# MCU.net
KiCad netlist of a schematic drawn in Altium Designer
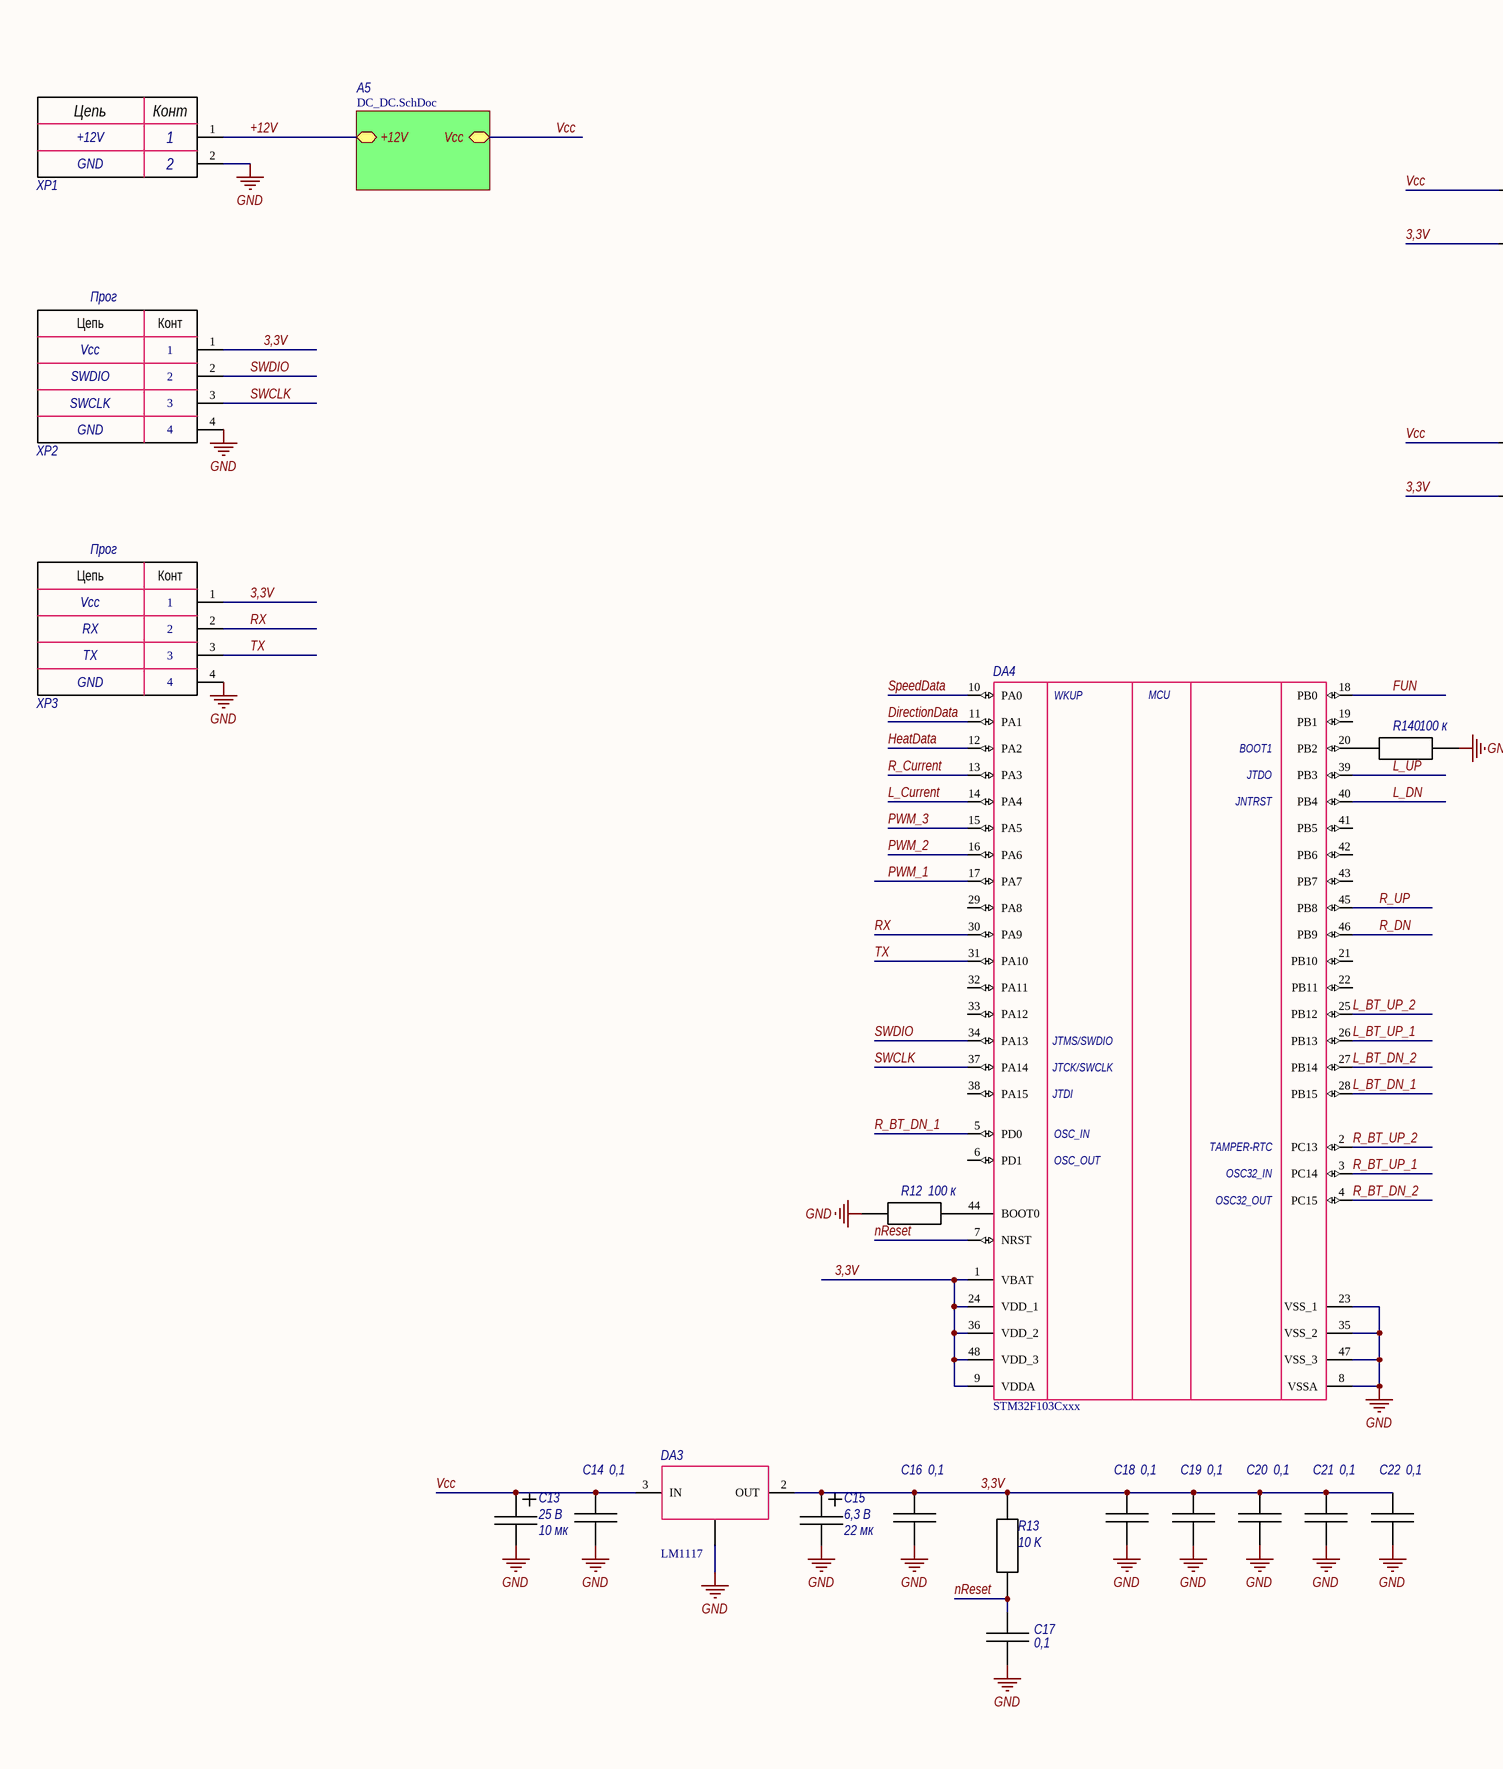
[diagram p0: MCU.SchDoc, left]
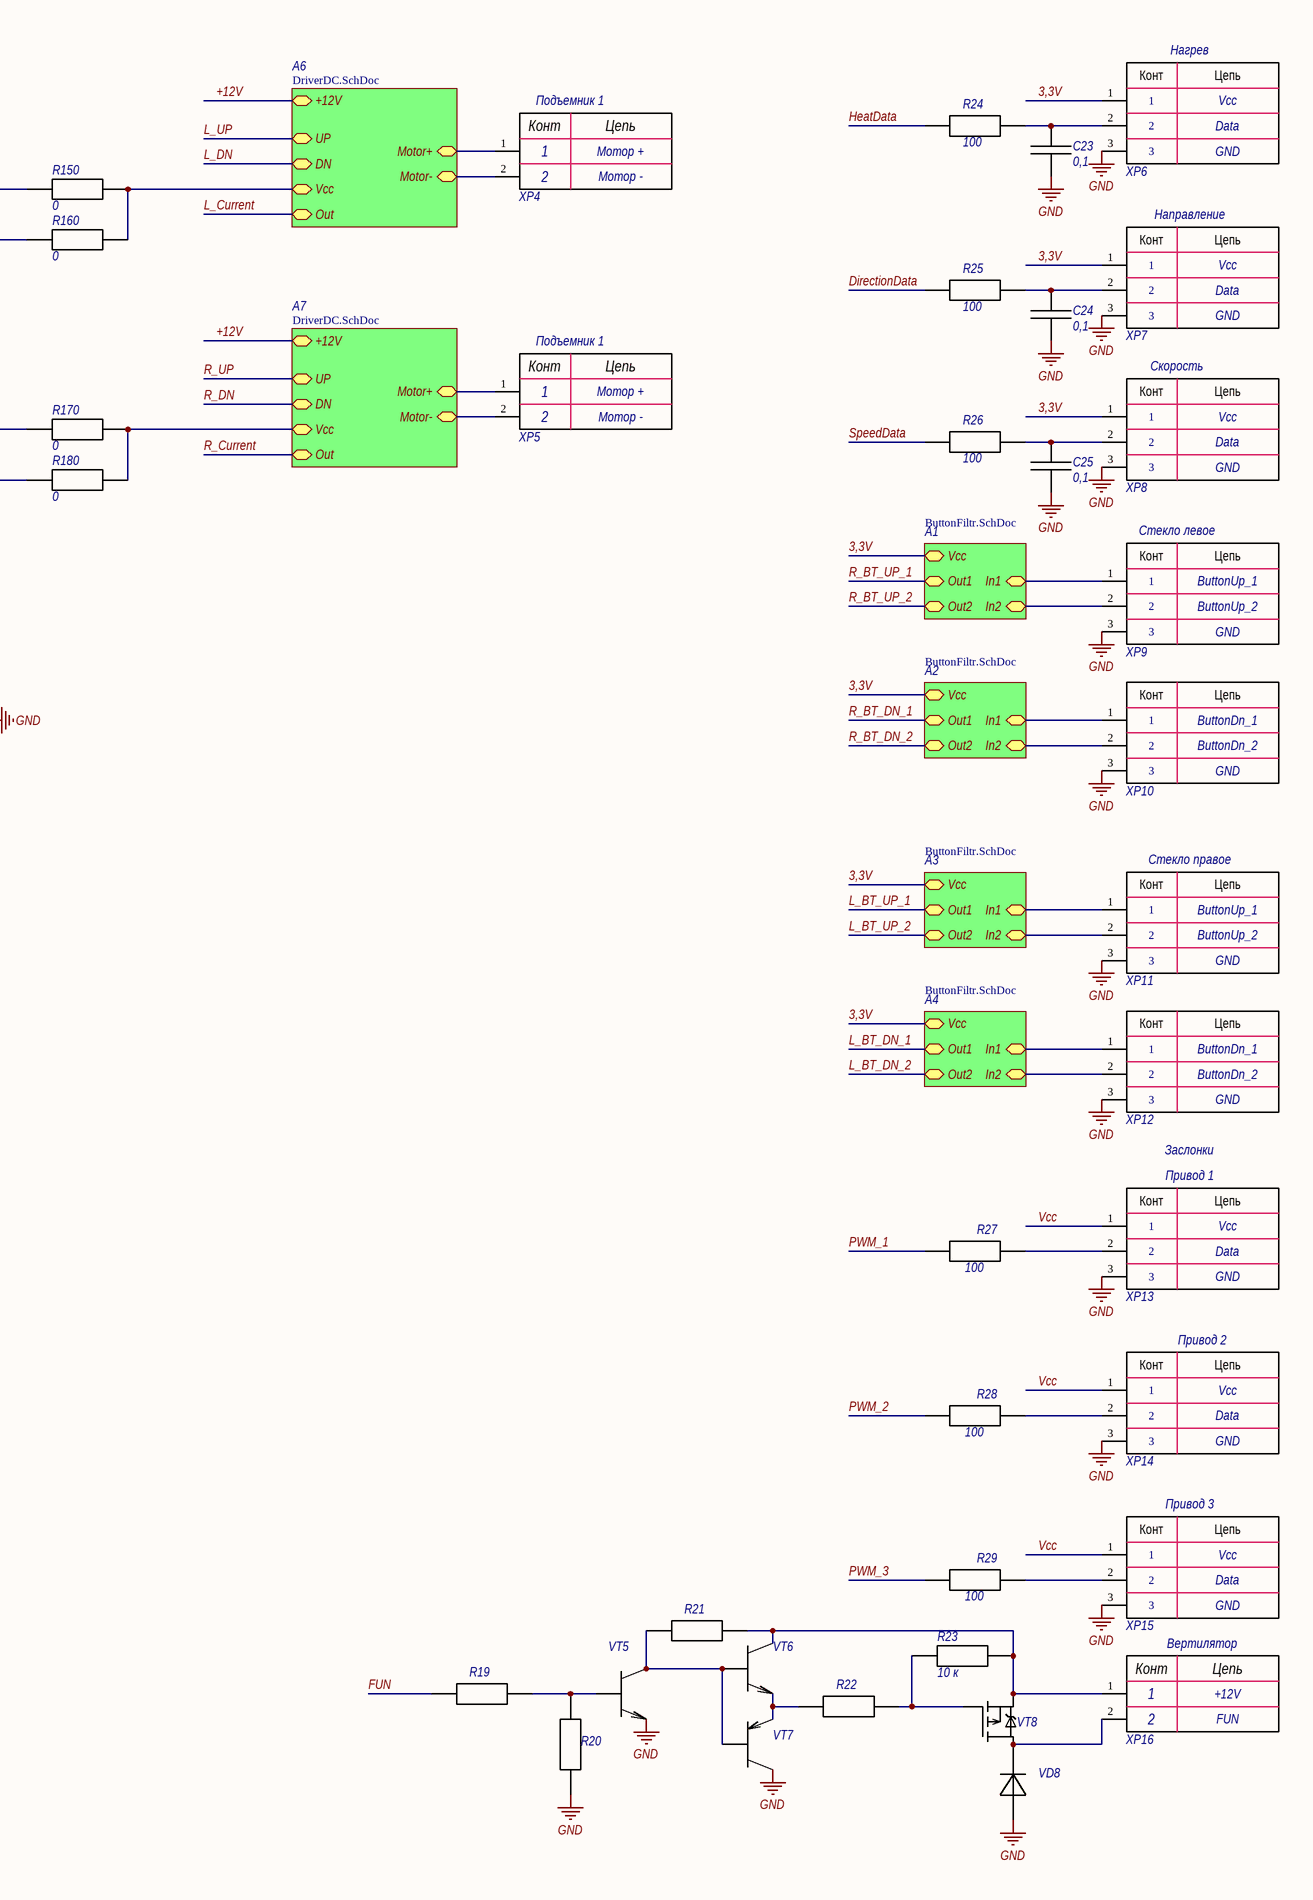
[diagram p1: MCU.SchDoc, right]

(export (version "E")
  (design (tool "Eeschema 10.0.6"))
  (components
    (comp (ref "C13")
      (value "Конденсаторы танталовые")
      (footprint "B-B")
      (fields
        (field (name "PART NUMBER") "Конденсатор танталовый 10 мкФ 25 В \"B\" +/- 10% T491B106K025AT \"KEMET\"")
        (field (name "MANUFACTURER") "\"KEMET\"")
        (field (name "MANUFACTURERPARTNUMBER") "T491B106K025AT")
        (field (name "POWER/VOLTAGE") "25 В")
        (field (name "VALUE SCH") "10 мк")
      )
      (libsource (lib "Library") (part "Конденсаторы танталовые"))
    )
    (comp (ref "C14")
      (value "Конденсаторы керамические")
      (footprint "C0603_autoMount")
      (fields
        (field (name "PART NUMBER") "Чип. керам. 0603 0,1 мкФ 50 В +/-10% X7R CC0603KKX7R9BB104 \"Yageo\"")
        (field (name "MANUFACTURER") "\"Yageo\"")
        (field (name "MANUFACTURERPARTNUMBER") "CC0603KKX7R9BB104")
        (field (name "VALUE SCH") "0,1")
      )
      (libsource (lib "Library") (part "Конденсаторы керамические"))
    )
    (comp (ref "C15")
      (value "Конденсаторы танталовые")
      (footprint "A-A")
      (fields
        (field (name "PART NUMBER") "Конденсатор танталовый 22 мкФ 6,3 В \"A\" +/- 10% TAJA226K006 \"Kyocera AVX\"")
        (field (name "MANUFACTURER") "\"Kyocera AVX\"")
        (field (name "MANUFACTURERPARTNUMBER") "TAJA226K006")
        (field (name "POWER/VOLTAGE") "6,3 В")
        (field (name "VALUE SCH") "22 мк")
      )
      (libsource (lib "Library") (part "Конденсаторы танталовые"))
    )
    (comp (ref "C16")
      (value "Конденсаторы керамические")
      (footprint "C0603_autoMount")
      (fields
        (field (name "PART NUMBER") "Чип. керам. 0603 0,1 мкФ 50 В +/-10% X7R CC0603KKX7R9BB104 \"Yageo\"")
        (field (name "MANUFACTURER") "\"Yageo\"")
        (field (name "MANUFACTURERPARTNUMBER") "CC0603KKX7R9BB104")
        (field (name "VALUE SCH") "0,1")
      )
      (libsource (lib "Library") (part "Конденсаторы керамические"))
    )
    (comp (ref "C17")
      (value "Конденсаторы керамические")
      (footprint "C0603_autoMount")
      (fields
        (field (name "PART NUMBER") "Чип. керам. 0603 0,1 мкФ 50 В +/-10% X7R CC0603KKX7R9BB104 \"Yageo\"")
        (field (name "MANUFACTURER") "\"Yageo\"")
        (field (name "MANUFACTURERPARTNUMBER") "CC0603KKX7R9BB104")
        (field (name "VALUE SCH") "0,1")
      )
      (libsource (lib "Library") (part "Конденсаторы керамические"))
    )
    (comp (ref "C18")
      (value "Конденсаторы керамические")
      (footprint "C0603_autoMount")
      (fields
        (field (name "PART NUMBER") "Чип. керам. 0603 0,1 мкФ 50 В +/-10% X7R CC0603KKX7R9BB104 \"Yageo\"")
        (field (name "MANUFACTURER") "\"Yageo\"")
        (field (name "MANUFACTURERPARTNUMBER") "CC0603KKX7R9BB104")
        (field (name "VALUE SCH") "0,1")
      )
      (libsource (lib "Library") (part "Конденсаторы керамические"))
    )
    (comp (ref "C19")
      (value "Конденсаторы керамические")
      (footprint "C0603_autoMount")
      (fields
        (field (name "PART NUMBER") "Чип. керам. 0603 0,1 мкФ 50 В +/-10% X7R CC0603KKX7R9BB104 \"Yageo\"")
        (field (name "MANUFACTURER") "\"Yageo\"")
        (field (name "MANUFACTURERPARTNUMBER") "CC0603KKX7R9BB104")
        (field (name "VALUE SCH") "0,1")
      )
      (libsource (lib "Library") (part "Конденсаторы керамические"))
    )
    (comp (ref "C20")
      (value "Конденсаторы керамические")
      (footprint "C0603_autoMount")
      (fields
        (field (name "PART NUMBER") "Чип. керам. 0603 0,1 мкФ 50 В +/-10% X7R CC0603KKX7R9BB104 \"Yageo\"")
        (field (name "MANUFACTURER") "\"Yageo\"")
        (field (name "MANUFACTURERPARTNUMBER") "CC0603KKX7R9BB104")
        (field (name "VALUE SCH") "0,1")
      )
      (libsource (lib "Library") (part "Конденсаторы керамические"))
    )
    (comp (ref "C21")
      (value "Конденсаторы керамические")
      (footprint "C0603_autoMount")
      (fields
        (field (name "PART NUMBER") "Чип. керам. 0603 0,1 мкФ 50 В +/-10% X7R CC0603KKX7R9BB104 \"Yageo\"")
        (field (name "MANUFACTURER") "\"Yageo\"")
        (field (name "MANUFACTURERPARTNUMBER") "CC0603KKX7R9BB104")
        (field (name "VALUE SCH") "0,1")
      )
      (libsource (lib "Library") (part "Конденсаторы керамические"))
    )
    (comp (ref "C22")
      (value "Конденсаторы керамические")
      (footprint "C0603_autoMount")
      (fields
        (field (name "PART NUMBER") "Чип. керам. 0603 0,1 мкФ 50 В +/-10% X7R CC0603KKX7R9BB104 \"Yageo\"")
        (field (name "MANUFACTURER") "\"Yageo\"")
        (field (name "MANUFACTURERPARTNUMBER") "CC0603KKX7R9BB104")
        (field (name "VALUE SCH") "0,1")
      )
      (libsource (lib "Library") (part "Конденсаторы керамические"))
    )
    (comp (ref "C23")
      (value "Конденсаторы керамические")
      (footprint "C0603_autoMount")
      (fields
        (field (name "PART NUMBER") "Чип. керам. 0603 0,1 мкФ 50 В +/-10% X7R CC0603KKX7R9BB104 \"Yageo\"")
        (field (name "MANUFACTURER") "\"Yageo\"")
        (field (name "MANUFACTURERPARTNUMBER") "CC0603KKX7R9BB104")
        (field (name "VALUE SCH") "0,1")
      )
      (libsource (lib "Library") (part "Конденсаторы керамические"))
    )
    (comp (ref "C24")
      (value "Конденсаторы керамические")
      (footprint "C0603_autoMount")
      (fields
        (field (name "PART NUMBER") "Чип. керам. 0603 0,1 мкФ 50 В +/-10% X7R CC0603KKX7R9BB104 \"Yageo\"")
        (field (name "MANUFACTURER") "\"Yageo\"")
        (field (name "MANUFACTURERPARTNUMBER") "CC0603KKX7R9BB104")
        (field (name "VALUE SCH") "0,1")
      )
      (libsource (lib "Library") (part "Конденсаторы керамические"))
    )
    (comp (ref "C25")
      (value "Конденсаторы керамические")
      (footprint "C0603_autoMount")
      (fields
        (field (name "PART NUMBER") "Чип. керам. 0603 0,1 мкФ 50 В +/-10% X7R CC0603KKX7R9BB104 \"Yageo\"")
        (field (name "MANUFACTURER") "\"Yageo\"")
        (field (name "MANUFACTURERPARTNUMBER") "CC0603KKX7R9BB104")
        (field (name "VALUE SCH") "0,1")
      )
      (libsource (lib "Library") (part "Конденсаторы керамические"))
    )
    (comp (ref "DA3")
      (value "LM1117")
      (footprint "SOT223")
      (fields
        (field (name "PART NUMBER") "Стабилизатор AMS1117-3.3 \"Advanced Monolithic Systems\" SOT-223")
        (field (name "MANUFACTURER") "\"Advanced Monolithic Systems\"")
        (field (name "MANUFACTURERPARTNUMBER") "AMS1117-3.3")
      )
      (libsource (lib "Library") (part "LM1117"))
    )
    (comp (ref "DA4")
      (value "STM32F103Cxxx")
      (footprint "TQFP_48")
      (fields
        (field (name "PART NUMBER") "Микросхема CH32F103C8T6 \"WinChip\" TQFP-48")
        (field (name "MANUFACTURER") "\"WinChip\"")
        (field (name "MANUFACTURERPARTNUMBER") "CH32F103C8T6")
      )
      (libsource (lib "Library") (part "STM32F103Cxxx"))
    )
    (comp (ref "R12")
      (value "Resistor")
      (footprint "R0603_autoMount")
      (fields
        (field (name "PART NUMBER") "Чип рез. 0603 100 кОм  +/-1% RC0603FR-07100KL \"Yageo\"")
        (field (name "MANUFACTURER") "\"Yageo\"")
        (field (name "MANUFACTURERPARTNUMBER") "RC0603FR-07100KL")
        (field (name "VALUE SСH") "100 к")
      )
      (libsource (lib "Library") (part "Resistor"))
    )
    (comp (ref "R13")
      (value "Resistor")
      (footprint "R0603_autoMount")
      (fields
        (field (name "PART NUMBER") "Чип рез. 0603 10 кОм  +/-1% RC0603FR-0710KL \"Yageo\"")
        (field (name "MANUFACTURER") "\"Yageo\"")
        (field (name "MANUFACTURERPARTNUMBER") "RC0603FR-0710KL")
        (field (name "VALUE EURO") "10 K")
      )
      (libsource (lib "Library") (part "Resistor"))
    )
    (comp (ref "R19")
      (value "Resistor")
      (footprint "R0603_autoMount")
      (fields
        (field (name "PART NUMBER") "Чип рез. 0603 1 кОм  +/-1% RC0603FR-071KL \"Yageo\"")
        (field (name "MANUFACTURER") "\"Yageo\"")
        (field (name "MANUFACTURERPARTNUMBER") "RC0603FR-071KL")
      )
      (libsource (lib "Library") (part "Resistor"))
    )
    (comp (ref "R20")
      (value "Resistor")
      (footprint "R0603_autoMount")
      (fields
        (field (name "PART NUMBER") "Чип рез. 0603 10 кОм  +/-1% RC0603FR-0710KL \"Yageo\"")
        (field (name "MANUFACTURER") "\"Yageo\"")
        (field (name "MANUFACTURERPARTNUMBER") "RC0603FR-0710KL")
      )
      (libsource (lib "") (part "Resistor_1"))
    )
    (comp (ref "R21")
      (value "Resistor")
      (footprint "R0603_autoMount")
      (fields
        (field (name "PART NUMBER") "Чип рез. 0603 1 кОм  +/-1% RC0603FR-071KL \"Yageo\"")
        (field (name "MANUFACTURER") "\"Yageo\"")
        (field (name "MANUFACTURERPARTNUMBER") "RC0603FR-071KL")
      )
      (libsource (lib "Library") (part "Resistor"))
    )
    (comp (ref "R22")
      (value "Resistor")
      (footprint "R0603_autoMount")
      (fields
        (field (name "PART NUMBER") "Чип рез. 0603 10 Ом  +/-1% RC0603FR-0710RL \"Yageo\"")
        (field (name "MANUFACTURER") "\"Yageo\"")
        (field (name "MANUFACTURERPARTNUMBER") "RC0603FR-0710RL")
      )
      (libsource (lib "Library") (part "Resistor"))
    )
    (comp (ref "R23")
      (value "Resistor")
      (footprint "R0603_autoMount")
      (fields
        (field (name "PART NUMBER") "Чип рез. 0603 10 кОм  +/-1% RC0603FR-0710KL \"Yageo\"")
        (field (name "MANUFACTURER") "\"Yageo\"")
        (field (name "MANUFACTURERPARTNUMBER") "RC0603FR-0710KL")
        (field (name "VALUE SСH") "10 к")
      )
      (libsource (lib "") (part "Resistor_2"))
    )
    (comp (ref "R24")
      (value "Resistor")
      (footprint "R0603_autoMount")
      (fields
        (field (name "PART NUMBER") "Чип рез. 0603 100 Ом  +/-1% RC0603FR-07100RL \"Yageo\"")
        (field (name "MANUFACTURER") "\"Yageo\"")
        (field (name "MANUFACTURERPARTNUMBER") "RC0603FR-07100RL")
        (field (name "VALUE SСH") "100")
      )
      (libsource (lib "") (part "Resistor_1"))
    )
    (comp (ref "R25")
      (value "Resistor")
      (footprint "R0603_autoMount")
      (fields
        (field (name "PART NUMBER") "Чип рез. 0603 100 Ом  +/-1% RC0603FR-07100RL \"Yageo\"")
        (field (name "MANUFACTURER") "\"Yageo\"")
        (field (name "MANUFACTURERPARTNUMBER") "RC0603FR-07100RL")
        (field (name "VALUE SСH") "100")
      )
      (libsource (lib "") (part "Resistor_1"))
    )
    (comp (ref "R26")
      (value "Resistor")
      (footprint "R0603_autoMount")
      (fields
        (field (name "PART NUMBER") "Чип рез. 0603 100 Ом  +/-1% RC0603FR-07100RL \"Yageo\"")
        (field (name "MANUFACTURER") "\"Yageo\"")
        (field (name "MANUFACTURERPARTNUMBER") "RC0603FR-07100RL")
        (field (name "VALUE SСH") "100")
      )
      (libsource (lib "") (part "Resistor_1"))
    )
    (comp (ref "R27")
      (value "Resistor")
      (footprint "R0603_autoMount")
      (fields
        (field (name "PART NUMBER") "Чип рез. 0603 100 Ом  +/-1% RC0603FR-07100RL \"Yageo\"")
        (field (name "MANUFACTURER") "\"Yageo\"")
        (field (name "MANUFACTURERPARTNUMBER") "RC0603FR-07100RL")
        (field (name "VALUE SСH") "100")
      )
      (libsource (lib "") (part "Resistor_1"))
    )
    (comp (ref "R28")
      (value "Resistor")
      (footprint "R0603_autoMount")
      (fields
        (field (name "PART NUMBER") "Чип рез. 0603 100 Ом  +/-1% RC0603FR-07100RL \"Yageo\"")
        (field (name "MANUFACTURER") "\"Yageo\"")
        (field (name "MANUFACTURERPARTNUMBER") "RC0603FR-07100RL")
        (field (name "VALUE SСH") "100")
      )
      (libsource (lib "") (part "Resistor_1"))
    )
    (comp (ref "R29")
      (value "Resistor")
      (footprint "R0603_autoMount")
      (fields
        (field (name "PART NUMBER") "Чип рез. 0603 100 Ом  +/-1% RC0603FR-07100RL \"Yageo\"")
        (field (name "MANUFACTURER") "\"Yageo\"")
        (field (name "MANUFACTURERPARTNUMBER") "RC0603FR-07100RL")
        (field (name "VALUE SСH") "100")
      )
      (libsource (lib "") (part "Resistor_1"))
    )
    (comp (ref "R140")
      (value "Resistor")
      (footprint "R0603_autoMount")
      (fields
        (field (name "PART NUMBER") "Чип рез. 0603 100 кОм  +/-1% RC0603FR-07100KL \"Yageo\"")
        (field (name "MANUFACTURER") "\"Yageo\"")
        (field (name "MANUFACTURERPARTNUMBER") "RC0603FR-07100KL")
        (field (name "VALUE SСH") "100 к")
      )
      (libsource (lib "Library") (part "Resistor"))
    )
    (comp (ref "R150")
      (value "Resistor")
      (footprint "R0603_autoMount")
      (fields
        (field (name "PART NUMBER") "Чип рез. 0603 0 Ом  +/-1% RC0603FR-070RL \"Yageo\"")
        (field (name "MANUFACTURER") "\"Yageo\"")
        (field (name "MANUFACTURERPARTNUMBER") "RC0603FR-070RL")
        (field (name "VALUE SСH") "0")
      )
      (libsource (lib "Library") (part "Resistor"))
    )
    (comp (ref "R160")
      (value "Resistor")
      (footprint "R0603_autoMount")
      (fields
        (field (name "PART NUMBER") "Чип рез. 0603 0 Ом  +/-1% RC0603FR-070RL \"Yageo\"")
        (field (name "MANUFACTURER") "\"Yageo\"")
        (field (name "MANUFACTURERPARTNUMBER") "RC0603FR-070RL")
        (field (name "VALUE SСH") "0")
      )
      (libsource (lib "Library") (part "Resistor"))
    )
    (comp (ref "R170")
      (value "Resistor")
      (footprint "R0603_autoMount")
      (fields
        (field (name "PART NUMBER") "Чип рез. 0603 0 Ом  +/-1% RC0603FR-070RL \"Yageo\"")
        (field (name "MANUFACTURER") "\"Yageo\"")
        (field (name "MANUFACTURERPARTNUMBER") "RC0603FR-070RL")
        (field (name "VALUE SСH") "0")
      )
      (libsource (lib "Library") (part "Resistor"))
    )
    (comp (ref "R180")
      (value "Resistor")
      (footprint "R0603_autoMount")
      (fields
        (field (name "PART NUMBER") "Чип рез. 0603 0 Ом  +/-1% RC0603FR-070RL \"Yageo\"")
        (field (name "MANUFACTURER") "\"Yageo\"")
        (field (name "MANUFACTURERPARTNUMBER") "RC0603FR-070RL")
        (field (name "VALUE SСH") "0")
      )
      (libsource (lib "Library") (part "Resistor"))
    )
    (comp (ref "VD8")
      (value "Diode")
      (footprint "DO-41_Vertical")
      (fields
        (field (name "PART NUMBER") "Диод 1N4007  DO-41")
        (field (name "MANUFACTURERPARTNUMBER") "1N4007")
      )
      (libsource (lib "Library") (part "Diode"))
    )
    (comp (ref "VT5")
      (value "npn")
      (footprint "SOT23-3")
      (fields
        (field (name "MANUFACTURERPARTNUMBER") "BC847B")
        (field (name "PART NUMBER") "Транзистор BC847B SOT23-3")
      )
      (libsource (lib "Library") (part "npn"))
    )
    (comp (ref "VT6")
      (value "npn")
      (footprint "SOT23-3")
      (fields
        (field (name "MANUFACTURERPARTNUMBER") "BC847B")
        (field (name "PART NUMBER") "Транзистор BC847B SOT23-3")
      )
      (libsource (lib "Library") (part "npn"))
    )
    (comp (ref "VT7")
      (value "pnp")
      (footprint "SOT23-3")
      (fields
        (field (name "MANUFACTURERPARTNUMBER") "BC857B")
        (field (name "PART NUMBER") "Транзистор BC857B SOT23-3")
      )
      (libsource (lib "Library") (part "pnp"))
    )
    (comp (ref "VT8")
      (value "P-Chanel Mosfet_dpak")
      (footprint "DPAK")
      (fields
        (field (name "PART NUMBER") "Транзистор NTD2955T4G D-PAK \"ON Semiconductor\"")
        (field (name "MANUFACTURER") "\"ON Semiconductor\"")
        (field (name "MANUFACTURERPARTNUMBER") "NTD2955T4G")
      )
      (libsource (lib "Library") (part "P-Chanel Mosfet_dpak"))
    )
    (comp (ref "XP1")
      (value "2pin")
      (footprint "301-021-12")
      (fields
        (field (name "MANUFACTURERPARTNUMBER") "XY301VA-5.0-2P-12")
        (field (name "MANUFACTURER") "\"Ningbo Xinya M&E\"")
        (field (name "PART NUMBER") "Клеммник XY301VA-5.0-2P-12 \"Ningbo Xinya M&E\"")
      )
      (libsource (lib "") (part "2pin_1"))
    )
    (comp (ref "XP2")
      (value "4pin")
      (footprint "PLS-4")
      (fields
        (field (name "MANUFACTURERPARTNUMBER") "DS1021-1*4SF11-B")
        (field (name "MANUFACTURER") "\"Connfly electronic\"")
        (field (name "PART NUMBER") "Вилка DS1021-1*4SF11-B PLS-4 \"Connfly electronic\"")
      )
      (libsource (lib "Library") (part "4pin"))
    )
    (comp (ref "XP3")
      (value "4pin")
      (footprint "PLS-4")
      (fields
        (field (name "MANUFACTURERPARTNUMBER") "DS1021-1*4SF11-B")
        (field (name "MANUFACTURER") "\"Connfly electronic\"")
        (field (name "PART NUMBER") "Вилка DS1021-1*4SF11-B PLS-4 \"Connfly electronic\"")
      )
      (libsource (lib "Library") (part "4pin"))
    )
    (comp (ref "XP4")
      (value "2pin")
      (footprint "301-021-12")
      (fields
        (field (name "MANUFACTURERPARTNUMBER") "XY301VA-5.0-2P-12")
        (field (name "MANUFACTURER") "\"Ningbo Xinya M&E\"")
        (field (name "PART NUMBER") "Клеммник XY301VA-5.0-2P-12 \"Ningbo Xinya M&E\"")
      )
      (libsource (lib "Library") (part "2pin"))
    )
    (comp (ref "XP5")
      (value "2pin")
      (footprint "301-021-12")
      (fields
        (field (name "MANUFACTURERPARTNUMBER") "XY301VA-5.0-2P-12")
        (field (name "MANUFACTURER") "\"Ningbo Xinya M&E\"")
        (field (name "PART NUMBER") "Клеммник XY301VA-5.0-2P-12 \"Ningbo Xinya M&E\"")
      )
      (libsource (lib "Library") (part "2pin"))
    )
    (comp (ref "XP6")
      (value "3pin")
      (footprint "CWF-3")
      (fields
        (field (name "MANUFACTURER") "\"Connfly electronic\"")
        (field (name "PART NUMBER") "Вилка  CWF-3 \"Connfly electronic\"")
      )
      (libsource (lib "Library") (part "3pin"))
    )
    (comp (ref "XP7")
      (value "3pin")
      (footprint "CWF-3")
      (fields
        (field (name "MANUFACTURER") "\"Connfly electronic\"")
        (field (name "PART NUMBER") "Вилка  CWF-3 \"Connfly electronic\"")
      )
      (libsource (lib "Library") (part "3pin"))
    )
    (comp (ref "XP8")
      (value "3pin")
      (footprint "CWF-3")
      (fields
        (field (name "MANUFACTURER") "\"Connfly electronic\"")
        (field (name "PART NUMBER") "Вилка  CWF-3 \"Connfly electronic\"")
      )
      (libsource (lib "Library") (part "3pin"))
    )
    (comp (ref "XP9")
      (value "3pin")
      (footprint "CWF-3")
      (fields
        (field (name "MANUFACTURER") "\"Connfly electronic\"")
        (field (name "PART NUMBER") "Вилка  CWF-3 \"Connfly electronic\"")
      )
      (libsource (lib "Library") (part "3pin"))
    )
    (comp (ref "XP10")
      (value "3pin")
      (footprint "CWF-3")
      (fields
        (field (name "MANUFACTURER") "\"Connfly electronic\"")
        (field (name "PART NUMBER") "Вилка  CWF-3 \"Connfly electronic\"")
      )
      (libsource (lib "Library") (part "3pin"))
    )
    (comp (ref "XP11")
      (value "3pin")
      (footprint "CWF-3")
      (fields
        (field (name "MANUFACTURER") "\"Connfly electronic\"")
        (field (name "PART NUMBER") "Вилка  CWF-3 \"Connfly electronic\"")
      )
      (libsource (lib "Library") (part "3pin"))
    )
    (comp (ref "XP12")
      (value "3pin")
      (footprint "CWF-3")
      (fields
        (field (name "MANUFACTURER") "\"Connfly electronic\"")
        (field (name "PART NUMBER") "Вилка  CWF-3 \"Connfly electronic\"")
      )
      (libsource (lib "Library") (part "3pin"))
    )
    (comp (ref "XP13")
      (value "3pin")
      (footprint "CWF-3")
      (fields
        (field (name "MANUFACTURER") "\"Connfly electronic\"")
        (field (name "PART NUMBER") "Вилка  CWF-3 \"Connfly electronic\"")
      )
      (libsource (lib "Library") (part "3pin"))
    )
    (comp (ref "XP14")
      (value "3pin")
      (footprint "CWF-3")
      (fields
        (field (name "MANUFACTURER") "\"Connfly electronic\"")
        (field (name "PART NUMBER") "Вилка  CWF-3 \"Connfly electronic\"")
      )
      (libsource (lib "Library") (part "3pin"))
    )
    (comp (ref "XP15")
      (value "3pin")
      (footprint "CWF-3")
      (fields
        (field (name "MANUFACTURER") "\"Connfly electronic\"")
        (field (name "PART NUMBER") "Вилка  CWF-3 \"Connfly electronic\"")
      )
      (libsource (lib "Library") (part "3pin"))
    )
    (comp (ref "XP16")
      (value "2pin")
      (footprint "301-021-12")
      (fields
        (field (name "MANUFACTURERPARTNUMBER") "XY301VA-5.0-2P-12")
        (field (name "MANUFACTURER") "\"Ningbo Xinya M&E\"")
        (field (name "PART NUMBER") "Клеммник XY301VA-5.0-2P-12 \"Ningbo Xinya M&E\"")
      )
      (libsource (lib "Library") (part "2pin"))
    )
  )
  (nets
    (net (code "1") (name "/+12V") (class "Default") (node (ref "XP1") (pin "1") (pintype "passive")))
    (net (code "2") (name "/3,3V") (class "Default")
      (node (ref "C15") (pin "1") (pinfunction "1_1") (pintype "passive"))
      (node (ref "C16") (pin "2") (pinfunction "2_2") (pintype "passive"))
      (node (ref "C18") (pin "2") (pinfunction "2_2") (pintype "passive"))
      (node (ref "C19") (pin "2") (pinfunction "2_2") (pintype "passive"))
      (node (ref "C20") (pin "2") (pinfunction "2_2") (pintype "passive"))
      (node (ref "C21") (pin "2") (pinfunction "2_2") (pintype "passive"))
      (node (ref "C22") (pin "2") (pinfunction "2_2") (pintype "passive"))
      (node (ref "DA3") (pin "2") (pinfunction "OUT_2") (pintype "passive"))
      (node (ref "DA4") (pin "1") (pinfunction "VBAT_1") (pintype "power_in"))
      (node (ref "DA4") (pin "24") (pinfunction "VDD_1_24") (pintype "power_in"))
      (node (ref "DA4") (pin "36") (pinfunction "VDD_2_36") (pintype "power_in"))
      (node (ref "DA4") (pin "48") (pinfunction "VDD_3_48") (pintype "power_in"))
      (node (ref "DA4") (pin "9") (pinfunction "VDDA_9") (pintype "power_in"))
      (node (ref "R13") (pin "1") (pinfunction "1_1") (pintype "passive"))
      (node (ref "R160") (pin "2") (pinfunction "2_2") (pintype "passive"))
      (node (ref "R180") (pin "2") (pinfunction "2_2") (pintype "passive"))
      (node (ref "XP2") (pin "1") (pintype "passive"))
      (node (ref "XP3") (pin "1") (pintype "passive"))
      (node (ref "XP6") (pin "1") (pintype "passive"))
      (node (ref "XP7") (pin "1") (pintype "passive"))
      (node (ref "XP8") (pin "1") (pintype "passive"))
    )
    (net (code "3") (name "/DirectionData") (class "Default")
      (node (ref "DA4") (pin "11") (pinfunction "PA1_11") (pintype "bidirectional"))
      (node (ref "R25") (pin "2") (pinfunction "2_2") (pintype "passive"))
    )
    (net (code "4") (name "/FUN") (class "Default")
      (node (ref "DA4") (pin "18") (pinfunction "PB0_18") (pintype "bidirectional"))
      (node (ref "R19") (pin "2") (pinfunction "2_2") (pintype "passive"))
    )
    (net (code "5") (name "/HeatData") (class "Default")
      (node (ref "DA4") (pin "12") (pinfunction "PA2_12") (pintype "bidirectional"))
      (node (ref "R24") (pin "2") (pinfunction "2_2") (pintype "passive"))
    )
    (net (code "6") (name "/In1") (class "Default") (node (ref "XP12") (pin "1") (pintype "passive")))
    (net (code "7") (name "/In1_1") (class "Default") (node (ref "XP9") (pin "1") (pintype "passive")))
    (net (code "8") (name "/In1_2") (class "Default") (node (ref "XP10") (pin "1") (pintype "passive")))
    (net (code "9") (name "/In1_3") (class "Default") (node (ref "XP11") (pin "1") (pintype "passive")))
    (net (code "10") (name "/In2") (class "Default") (node (ref "XP9") (pin "2") (pintype "passive")))
    (net (code "11") (name "/In2_1") (class "Default") (node (ref "XP10") (pin "2") (pintype "passive")))
    (net (code "12") (name "/In2_2") (class "Default") (node (ref "XP11") (pin "2") (pintype "passive")))
    (net (code "13") (name "/In2_3") (class "Default") (node (ref "XP12") (pin "2") (pintype "passive")))
    (net (code "14") (name "/L_BT_DN_1") (class "Default")
      (node (ref "DA4") (pin "28") (pinfunction "PB15_28") (pintype "bidirectional"))
    )
    (net (code "15") (name "/L_BT_DN_2") (class "Default")
      (node (ref "DA4") (pin "27") (pinfunction "PB14_27") (pintype "bidirectional"))
    )
    (net (code "16") (name "/L_BT_UP_1") (class "Default")
      (node (ref "DA4") (pin "26") (pinfunction "PB13_26") (pintype "bidirectional"))
    )
    (net (code "17") (name "/L_BT_UP_2") (class "Default")
      (node (ref "DA4") (pin "25") (pinfunction "PB12_25") (pintype "bidirectional"))
    )
    (net (code "18") (name "/L_Current") (class "Default")
      (node (ref "DA4") (pin "14") (pinfunction "PA4_14") (pintype "bidirectional"))
    )
    (net (code "19") (name "/L_DN") (class "Default")
      (node (ref "DA4") (pin "40") (pinfunction "PB4_40") (pintype "bidirectional"))
    )
    (net (code "20") (name "/L_UP") (class "Default")
      (node (ref "DA4") (pin "39") (pinfunction "PB3_39") (pintype "bidirectional"))
    )
    (net (code "21") (name "/Motor+") (class "Default") (node (ref "XP5") (pin "1") (pintype "passive")))
    (net (code "22") (name "/Motor+_1") (class "Default") (node (ref "XP4") (pin "1") (pintype "passive")))
    (net (code "23") (name "/Motor-") (class "Default") (node (ref "XP5") (pin "2") (pintype "passive")))
    (net (code "24") (name "/Motor-_1") (class "Default") (node (ref "XP4") (pin "2") (pintype "passive")))
    (net (code "25") (name "/PWM_1") (class "Default")
      (node (ref "DA4") (pin "17") (pinfunction "PA7_17") (pintype "bidirectional"))
      (node (ref "R27") (pin "2") (pinfunction "2_2") (pintype "passive"))
    )
    (net (code "26") (name "/PWM_2") (class "Default")
      (node (ref "DA4") (pin "16") (pinfunction "PA6_16") (pintype "bidirectional"))
      (node (ref "R28") (pin "2") (pinfunction "2_2") (pintype "passive"))
    )
    (net (code "27") (name "/PWM_3") (class "Default")
      (node (ref "DA4") (pin "15") (pinfunction "PA5_15") (pintype "bidirectional"))
      (node (ref "R29") (pin "2") (pinfunction "2_2") (pintype "passive"))
    )
    (net (code "28") (name "/RX") (class "Default")
      (node (ref "DA4") (pin "30") (pinfunction "PA9_30") (pintype "bidirectional"))
      (node (ref "XP3") (pin "2") (pintype "passive"))
    )
    (net (code "29") (name "/R_BT_DN_1") (class "Default")
      (node (ref "DA4") (pin "5") (pinfunction "PD0_5") (pintype "bidirectional"))
    )
    (net (code "30") (name "/R_BT_DN_2") (class "Default")
      (node (ref "DA4") (pin "4") (pinfunction "PC15_4") (pintype "bidirectional"))
    )
    (net (code "31") (name "/R_BT_UP_1") (class "Default")
      (node (ref "DA4") (pin "3") (pinfunction "PC14_3") (pintype "bidirectional"))
    )
    (net (code "32") (name "/R_BT_UP_2") (class "Default")
      (node (ref "DA4") (pin "2") (pinfunction "PC13_2") (pintype "bidirectional"))
    )
    (net (code "33") (name "/R_Current") (class "Default")
      (node (ref "DA4") (pin "13") (pinfunction "PA3_13") (pintype "bidirectional"))
    )
    (net (code "34") (name "/R_DN") (class "Default")
      (node (ref "DA4") (pin "46") (pinfunction "PB9_46") (pintype "bidirectional"))
    )
    (net (code "35") (name "/R_UP") (class "Default")
      (node (ref "DA4") (pin "45") (pinfunction "PB8_45") (pintype "bidirectional"))
    )
    (net (code "36") (name "/SWCLK") (class "Default")
      (node (ref "DA4") (pin "37") (pinfunction "PA14_37") (pintype "bidirectional"))
      (node (ref "XP2") (pin "3") (pintype "passive"))
    )
    (net (code "37") (name "/SWDIO") (class "Default")
      (node (ref "DA4") (pin "34") (pinfunction "PA13_34") (pintype "bidirectional"))
      (node (ref "XP2") (pin "2") (pintype "passive"))
    )
    (net (code "38") (name "/SpeedData") (class "Default")
      (node (ref "DA4") (pin "10") (pinfunction "PA0_10") (pintype "bidirectional"))
      (node (ref "R26") (pin "2") (pinfunction "2_2") (pintype "passive"))
    )
    (net (code "39") (name "/TX") (class "Default")
      (node (ref "DA4") (pin "31") (pinfunction "PA10_31") (pintype "bidirectional"))
      (node (ref "XP3") (pin "3") (pintype "passive"))
    )
    (net (code "40") (name "/Vcc") (class "Default")
      (node (ref "C13") (pin "1") (pinfunction "1_1") (pintype "passive"))
      (node (ref "C14") (pin "2") (pinfunction "2_2") (pintype "passive"))
      (node (ref "DA3") (pin "3") (pinfunction "IN_3") (pintype "passive"))
      (node (ref "R150") (pin "2") (pinfunction "2_2") (pintype "passive"))
      (node (ref "R170") (pin "2") (pinfunction "2_2") (pintype "passive"))
      (node (ref "XP13") (pin "1") (pintype "passive"))
      (node (ref "XP14") (pin "1") (pintype "passive"))
      (node (ref "XP15") (pin "1") (pintype "passive"))
    )
    (net (code "41") (name "/Vcc_1") (class "Default")
      (node (ref "R170") (pin "1") (pinfunction "1_1") (pintype "passive"))
      (node (ref "R180") (pin "1") (pinfunction "1_1") (pintype "passive"))
    )
    (net (code "42") (name "/Vcc_2") (class "Default")
      (node (ref "R150") (pin "1") (pinfunction "1_1") (pintype "passive"))
      (node (ref "R160") (pin "1") (pinfunction "1_1") (pintype "passive"))
    )
    (net (code "43") (name "/nReset") (class "Default")
      (node (ref "C17") (pin "2") (pinfunction "2_2") (pintype "passive"))
      (node (ref "DA4") (pin "7") (pinfunction "NRST_7") (pintype "bidirectional"))
      (node (ref "R13") (pin "2") (pinfunction "2_2") (pintype "passive"))
    )
    (net (code "44") (name "GND") (class "Default")
      (node (ref "C13") (pin "2") (pinfunction "2_2") (pintype "passive"))
      (node (ref "C14") (pin "1") (pinfunction "1_1") (pintype "passive"))
      (node (ref "C15") (pin "2") (pinfunction "2_2") (pintype "passive"))
      (node (ref "C16") (pin "1") (pinfunction "1_1") (pintype "passive"))
      (node (ref "C17") (pin "1") (pinfunction "1_1") (pintype "passive"))
      (node (ref "C18") (pin "1") (pinfunction "1_1") (pintype "passive"))
      (node (ref "C19") (pin "1") (pinfunction "1_1") (pintype "passive"))
      (node (ref "C20") (pin "1") (pinfunction "1_1") (pintype "passive"))
      (node (ref "C21") (pin "1") (pinfunction "1_1") (pintype "passive"))
      (node (ref "C22") (pin "1") (pinfunction "1_1") (pintype "passive"))
      (node (ref "C23") (pin "1") (pinfunction "1_1") (pintype "passive"))
      (node (ref "C24") (pin "1") (pinfunction "1_1") (pintype "passive"))
      (node (ref "C25") (pin "1") (pinfunction "1_1") (pintype "passive"))
      (node (ref "DA3") (pin "1") (pinfunction "GND_1") (pintype "passive"))
      (node (ref "DA4") (pin "23") (pinfunction "VSS_1_23") (pintype "power_in"))
      (node (ref "DA4") (pin "35") (pinfunction "VSS_2_35") (pintype "power_in"))
      (node (ref "DA4") (pin "47") (pinfunction "VSS_3_47") (pintype "power_in"))
      (node (ref "DA4") (pin "8") (pinfunction "VSSA_8") (pintype "power_in"))
      (node (ref "R12") (pin "2") (pinfunction "2_2") (pintype "passive"))
      (node (ref "R140") (pin "1") (pinfunction "1_1") (pintype "passive"))
      (node (ref "R20") (pin "2") (pinfunction "2_2") (pintype "passive"))
      (node (ref "VD8") (pin "2") (pinfunction "2_2") (pintype "passive"))
      (node (ref "VT5") (pin "2") (pinfunction "E_2") (pintype "passive"))
      (node (ref "VT7") (pin "3") (pinfunction "C_3") (pintype "passive"))
      (node (ref "XP1") (pin "2") (pintype "passive"))
      (node (ref "XP10") (pin "3") (pintype "passive"))
      (node (ref "XP11") (pin "3") (pintype "passive"))
      (node (ref "XP12") (pin "3") (pintype "passive"))
      (node (ref "XP13") (pin "3") (pintype "passive"))
      (node (ref "XP14") (pin "3") (pintype "passive"))
      (node (ref "XP15") (pin "3") (pintype "passive"))
      (node (ref "XP2") (pin "4") (pintype "passive"))
      (node (ref "XP3") (pin "4") (pintype "passive"))
      (node (ref "XP6") (pin "3") (pintype "passive"))
      (node (ref "XP7") (pin "3") (pintype "passive"))
      (node (ref "XP8") (pin "3") (pintype "passive"))
      (node (ref "XP9") (pin "3") (pintype "passive"))
    )
    (net (code "45") (name "Net-(C23-Pad2)") (class "Default")
      (node (ref "C23") (pin "2") (pinfunction "2_2") (pintype "passive"))
      (node (ref "R24") (pin "1") (pinfunction "1_1") (pintype "passive"))
      (node (ref "XP6") (pin "2") (pintype "passive"))
    )
    (net (code "46") (name "Net-(C24-Pad2)") (class "Default")
      (node (ref "C24") (pin "2") (pinfunction "2_2") (pintype "passive"))
      (node (ref "R25") (pin "1") (pinfunction "1_1") (pintype "passive"))
      (node (ref "XP7") (pin "2") (pintype "passive"))
    )
    (net (code "47") (name "Net-(C25-Pad2)") (class "Default")
      (node (ref "C25") (pin "2") (pinfunction "2_2") (pintype "passive"))
      (node (ref "R26") (pin "1") (pinfunction "1_1") (pintype "passive"))
      (node (ref "XP8") (pin "2") (pintype "passive"))
    )
    (net (code "48") (name "Net-(DA4-BOOT0)") (class "Default")
      (node (ref "DA4") (pin "44") (pinfunction "BOOT0_44") (pintype "passive"))
      (node (ref "R12") (pin "1") (pinfunction "1_1") (pintype "passive"))
    )
    (net (code "49") (name "Net-(DA4-PB2)") (class "Default")
      (node (ref "DA4") (pin "20") (pinfunction "PB2_20") (pintype "bidirectional"))
      (node (ref "R140") (pin "2") (pinfunction "2_2") (pintype "passive"))
    )
    (net (code "50") (name "Net-(R27-Pad1)") (class "Default")
      (node (ref "R27") (pin "1") (pinfunction "1_1") (pintype "passive"))
      (node (ref "XP13") (pin "2") (pintype "passive"))
    )
    (net (code "51") (name "Net-(R28-Pad1)") (class "Default")
      (node (ref "R28") (pin "1") (pinfunction "1_1") (pintype "passive"))
      (node (ref "XP14") (pin "2") (pintype "passive"))
    )
    (net (code "52") (name "Net-(R29-Pad1)") (class "Default")
      (node (ref "R29") (pin "1") (pinfunction "1_1") (pintype "passive"))
      (node (ref "XP15") (pin "2") (pintype "passive"))
    )
    (net (code "53") (name "Net-(VT5-B)") (class "Default")
      (node (ref "R19") (pin "1") (pinfunction "1_1") (pintype "passive"))
      (node (ref "R20") (pin "1") (pinfunction "1_1") (pintype "passive"))
      (node (ref "VT5") (pin "1") (pinfunction "B_1") (pintype "passive"))
    )
    (net (code "54") (name "Net-(VT5-C)") (class "Default")
      (node (ref "R21") (pin "2") (pinfunction "2_2") (pintype "passive"))
      (node (ref "VT5") (pin "3") (pinfunction "C_3") (pintype "passive"))
      (node (ref "VT6") (pin "1") (pinfunction "B_1") (pintype "passive"))
      (node (ref "VT7") (pin "1") (pinfunction "B_1") (pintype "passive"))
    )
    (net (code "55") (name "Net-(VT6-C)") (class "Default")
      (node (ref "R21") (pin "1") (pinfunction "1_1") (pintype "passive"))
      (node (ref "R23") (pin "2") (pinfunction "2_2") (pintype "passive"))
      (node (ref "VT6") (pin "3") (pinfunction "C_3") (pintype "passive"))
      (node (ref "VT8") (pin "3") (pinfunction "S_3") (pintype "passive"))
      (node (ref "XP16") (pin "1") (pintype "passive"))
    )
    (net (code "56") (name "Net-(VT6-E)") (class "Default")
      (node (ref "R22") (pin "2") (pinfunction "2_2") (pintype "passive"))
      (node (ref "VT6") (pin "2") (pinfunction "E_2") (pintype "passive"))
      (node (ref "VT7") (pin "2") (pinfunction "E_2") (pintype "passive"))
    )
    (net (code "57") (name "Net-(VT8-D)") (class "Default")
      (node (ref "VD8") (pin "1") (pinfunction "1_1") (pintype "passive"))
      (node (ref "VT8") (pin "2") (pinfunction "D_2") (pintype "passive"))
      (node (ref "XP16") (pin "2") (pintype "passive"))
    )
    (net (code "58") (name "Net-(VT8-G)") (class "Default")
      (node (ref "R22") (pin "1") (pinfunction "1_1") (pintype "passive"))
      (node (ref "R23") (pin "1") (pinfunction "1_1") (pintype "passive"))
      (node (ref "VT8") (pin "1") (pinfunction "G_1") (pintype "passive"))
    )
    (net (code "59") (name "unconnected-(DA4-PA8-Pad29)") (class "Default")
      (node (ref "DA4") (pin "29") (pinfunction "PA8_29") (pintype "bidirectional"))
    )
    (net (code "60") (name "unconnected-(DA4-PA11-Pad32)") (class "Default")
      (node (ref "DA4") (pin "32") (pinfunction "PA11_32") (pintype "bidirectional"))
    )
    (net (code "61") (name "unconnected-(DA4-PA12-Pad33)") (class "Default")
      (node (ref "DA4") (pin "33") (pinfunction "PA12_33") (pintype "bidirectional"))
    )
    (net (code "62") (name "unconnected-(DA4-PA15-Pad38)") (class "Default")
      (node (ref "DA4") (pin "38") (pinfunction "PA15_38") (pintype "bidirectional"))
    )
    (net (code "63") (name "unconnected-(DA4-PB1-Pad19)") (class "Default")
      (node (ref "DA4") (pin "19") (pinfunction "PB1_19") (pintype "bidirectional"))
    )
    (net (code "64") (name "unconnected-(DA4-PB5-Pad41)") (class "Default")
      (node (ref "DA4") (pin "41") (pinfunction "PB5_41") (pintype "bidirectional"))
    )
    (net (code "65") (name "unconnected-(DA4-PB6-Pad42)") (class "Default")
      (node (ref "DA4") (pin "42") (pinfunction "PB6_42") (pintype "bidirectional"))
    )
    (net (code "66") (name "unconnected-(DA4-PB7-Pad43)") (class "Default")
      (node (ref "DA4") (pin "43") (pinfunction "PB7_43") (pintype "bidirectional"))
    )
    (net (code "67") (name "unconnected-(DA4-PB10-Pad21)") (class "Default")
      (node (ref "DA4") (pin "21") (pinfunction "PB10_21") (pintype "bidirectional"))
    )
    (net (code "68") (name "unconnected-(DA4-PB11-Pad22)") (class "Default")
      (node (ref "DA4") (pin "22") (pinfunction "PB11_22") (pintype "bidirectional"))
    )
    (net (code "69") (name "unconnected-(DA4-PD1-Pad6)") (class "Default")
      (node (ref "DA4") (pin "6") (pinfunction "PD1_6") (pintype "bidirectional"))
    )
  )
)
